# encoder.net
KiCad netlist of a schematic drawn in EAGLE
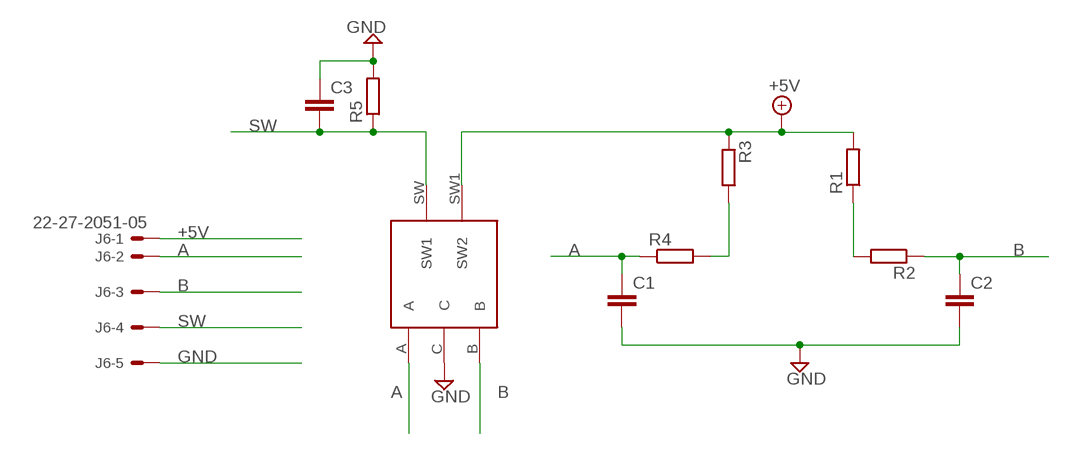
[diagram p0: schematic, sheet 1]

(export (version "E")
  (design (tool "Eeschema 10.0.6"))
  (components
    (comp (ref "C1")
      (value "C-EUC0805")
      (footprint "eagle-import:C0805")
      (libsource (lib "eagle-import") (part "C-EUC0805"))
    )
    (comp (ref "C2")
      (value "C-EUC0805")
      (footprint "eagle-import:C0805")
      (libsource (lib "eagle-import") (part "C-EUC0805"))
    )
    (comp (ref "C3")
      (value "C-EUC0805")
      (footprint "eagle-import:C0805")
      (libsource (lib "eagle-import") (part "C-EUC0805"))
    )
    (comp (ref "J6")
      (value "22-27-2051-05")
      (footprint "eagle-import:6410-05")
      (fields (field (name "MF") "MOLEX"))
      (libsource (lib "eagle-import") (part "22-?-0527-2051"))
    )
    (comp (ref "R1")
      (value "R-EU_MELF0204W")
      (footprint "eagle-import:MINI_MELF-0204W")
      (libsource (lib "eagle-import") (part "R-EU_MELF0204W"))
    )
    (comp (ref "R2")
      (value "R-EU_MELF0204W")
      (footprint "eagle-import:MINI_MELF-0204W")
      (libsource (lib "eagle-import") (part "R-EU_MELF0204W"))
    )
    (comp (ref "R3")
      (value "R-EU_MELF0204W")
      (footprint "eagle-import:MINI_MELF-0204W")
      (libsource (lib "eagle-import") (part "R-EU_MELF0204W"))
    )
    (comp (ref "R4")
      (value "R-EU_MELF0204W")
      (footprint "eagle-import:MINI_MELF-0204W")
      (libsource (lib "eagle-import") (part "R-EU_MELF0204W"))
    )
    (comp (ref "R5")
      (value "R-EU_MELF0204W")
      (footprint "eagle-import:MINI_MELF-0204W")
      (libsource (lib "eagle-import") (part "R-EU_MELF0204W"))
    )
    (comp (ref "U$1")
      (value "BOURNS_ROTARY")
      (footprint "eagle-import:BOURNS_ROTARY")
      (libsource (lib "eagle-import") (part "BOURNS_ROTARY"))
    )
  )
  (nets
    (net (code "1") (name "+5V") (class "Default")
      (node (ref "J6") (pin "1") (pinfunction "S_1") (pintype "passive"))
      (node (ref "R1") (pin "2") (pinfunction "2_2") (pintype "passive"))
      (node (ref "R3") (pin "1") (pinfunction "1_1") (pintype "passive"))
      (node (ref "U$1") (pin "SW1") (pinfunction "SW2_SW1") (pintype "bidirectional"))
    )
    (net (code "2") (name "/A") (class "Default")
      (node (ref "C1") (pin "1") (pinfunction "1_1") (pintype "passive"))
      (node (ref "J6") (pin "2") (pinfunction "S_2") (pintype "passive"))
      (node (ref "R4") (pin "1") (pinfunction "1_1") (pintype "passive"))
      (node (ref "U$1") (pin "A") (pinfunction "A_A") (pintype "bidirectional"))
    )
    (net (code "3") (name "/B") (class "Default")
      (node (ref "C2") (pin "1") (pinfunction "1_1") (pintype "passive"))
      (node (ref "J6") (pin "3") (pinfunction "S_3") (pintype "passive"))
      (node (ref "R2") (pin "1") (pinfunction "1_1") (pintype "passive"))
      (node (ref "U$1") (pin "B") (pinfunction "B_B") (pintype "bidirectional"))
    )
    (net (code "4") (name "/SW") (class "Default")
      (node (ref "C3") (pin "2") (pinfunction "2_2") (pintype "passive"))
      (node (ref "J6") (pin "4") (pinfunction "S_4") (pintype "passive"))
      (node (ref "R5") (pin "1") (pinfunction "1_1") (pintype "passive"))
      (node (ref "U$1") (pin "SW") (pinfunction "SW1_SW") (pintype "bidirectional"))
    )
    (net (code "5") (name "GND") (class "Default")
      (node (ref "C1") (pin "2") (pinfunction "2_2") (pintype "passive"))
      (node (ref "C2") (pin "2") (pinfunction "2_2") (pintype "passive"))
      (node (ref "C3") (pin "1") (pinfunction "1_1") (pintype "passive"))
      (node (ref "J6") (pin "5") (pinfunction "S_5") (pintype "passive"))
      (node (ref "R5") (pin "2") (pinfunction "2_2") (pintype "passive"))
      (node (ref "U$1") (pin "C") (pinfunction "C_C") (pintype "bidirectional"))
    )
    (net (code "6") (name "Net-(R1-Pad1)") (class "Default")
      (node (ref "R1") (pin "1") (pinfunction "1_1") (pintype "passive"))
      (node (ref "R2") (pin "2") (pinfunction "2_2") (pintype "passive"))
    )
    (net (code "7") (name "Net-(R3-Pad2)") (class "Default")
      (node (ref "R3") (pin "2") (pinfunction "2_2") (pintype "passive"))
      (node (ref "R4") (pin "2") (pinfunction "2_2") (pintype "passive"))
    )
  )
)
